# 02_-_CPU.net
KiCad netlist of a schematic drawn in Altium Designer
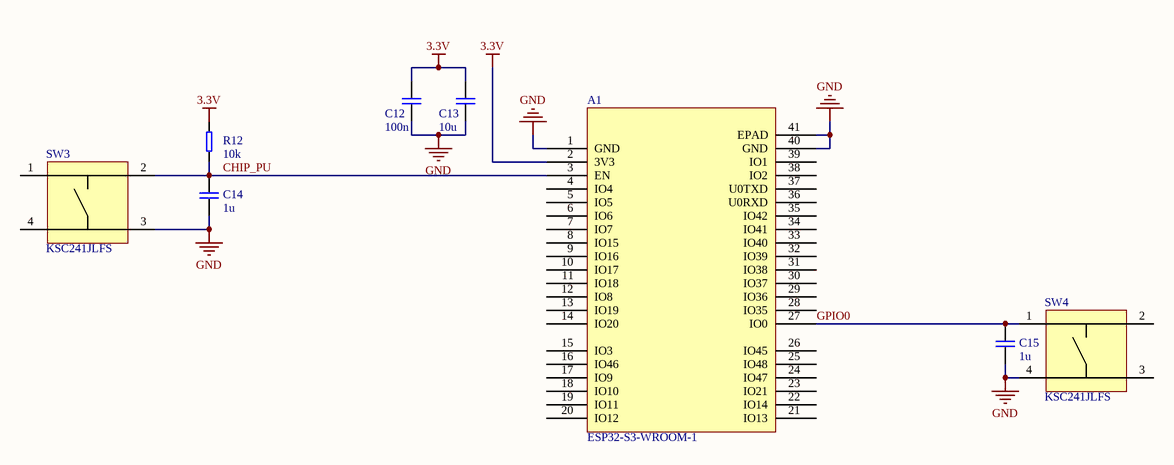
[diagram p0: [02] - CPU.SchDoc]

(export (version "E")
  (design (tool "Eeschema 10.0.6"))
  (components
    (comp (ref "A1")
      (value "ESP32-S3-WROOM-1")
      (footprint "ESP32-S3-WROOM-1")
      (description "2.4 GHz Wi-Fi (802.11 b/g/n) and Bluetooth® 5 (LE) module")
      (fields (field (name "MANUFACTURER") "espressif"))
      (libsource (lib "1") (part "ESP32-S3-WROOM-1"))
    )
    (comp (ref "C12")
      (value "100n")
      (footprint "C0603")
      (description "CAPACITOR")
      (libsource (lib "1") (part "Cap"))
    )
    (comp (ref "C13")
      (value "10u")
      (footprint "C0603")
      (description "CAPACITOR")
      (libsource (lib "1") (part "Cap"))
    )
    (comp (ref "C14")
      (value "1u")
      (footprint "C0603")
      (description "CAPACITOR")
      (libsource (lib "1") (part "Cap"))
    )
    (comp (ref "C15")
      (value "1u")
      (footprint "C0603")
      (description "CAPACITOR")
      (libsource (lib "1") (part "Cap"))
    )
    (comp (ref "R12")
      (value "10k")
      (footprint "R0603")
      (description "RESISTOR")
      (libsource (lib "1") (part "Res"))
    )
    (comp (ref "SW3")
      (value "KSC241JLFS")
      (footprint "KSC241JLFS")
      (description "SWITCH TACTILE SPST-NO 50mA @ 32VDC")
      (fields (field (name "MANUFACTURER") "C&K"))
      (libsource (lib "1") (part "KSC241JLFS"))
    )
    (comp (ref "SW4")
      (value "KSC241JLFS")
      (footprint "KSC241JLFS")
      (description "SWITCH TACTILE SPST-NO 50mA @ 32VDC")
      (fields (field (name "MANUFACTURER") "C&K"))
      (libsource (lib "1") (part "KSC241JLFS"))
    )
  )
  (nets
    (net (code "1") (name "/CHIP_PU") (class "Default")
      (node (ref "A1") (pin "3") (pinfunction "EN_3") (pintype "passive"))
      (node (ref "C14") (pin "1") (pinfunction "1_1") (pintype "passive"))
      (node (ref "R12") (pin "1") (pinfunction "1_1") (pintype "passive"))
      (node (ref "SW3") (pin "2") (pinfunction "2_2") (pintype "passive"))
    )
    (net (code "2") (name "/GPIO0") (class "Default")
      (node (ref "A1") (pin "27") (pinfunction "IO0_27") (pintype "passive"))
      (node (ref "C15") (pin "1") (pinfunction "1_1") (pintype "passive"))
      (node (ref "SW4") (pin "1") (pinfunction "1_1") (pintype "passive"))
    )
    (net (code "3") (name "3.3V") (class "Default")
      (node (ref "A1") (pin "2") (pinfunction "3V3_2") (pintype "passive"))
      (node (ref "C12") (pin "1") (pinfunction "1_1") (pintype "passive"))
      (node (ref "C13") (pin "1") (pinfunction "1_1") (pintype "passive"))
      (node (ref "R12") (pin "2") (pinfunction "2_2") (pintype "passive"))
    )
    (net (code "4") (name "GND") (class "Default")
      (node (ref "A1") (pin "1") (pinfunction "GND_1") (pintype "passive"))
      (node (ref "A1") (pin "40") (pinfunction "GND_40") (pintype "passive"))
      (node (ref "A1") (pin "41") (pinfunction "EPAD_41") (pintype "passive"))
      (node (ref "C12") (pin "2") (pinfunction "2_2") (pintype "passive"))
      (node (ref "C13") (pin "2") (pinfunction "2_2") (pintype "passive"))
      (node (ref "C14") (pin "2") (pinfunction "2_2") (pintype "passive"))
      (node (ref "C15") (pin "2") (pinfunction "2_2") (pintype "passive"))
      (node (ref "SW3") (pin "3") (pinfunction "3_3") (pintype "passive"))
      (node (ref "SW4") (pin "4") (pinfunction "4_4") (pintype "passive"))
    )
    (net (code "5") (name "unconnected-(A1-IO1-Pad39)") (class "Default")
      (node (ref "A1") (pin "39") (pinfunction "IO1_39") (pintype "passive"))
    )
    (net (code "6") (name "unconnected-(A1-IO2-Pad38)") (class "Default")
      (node (ref "A1") (pin "38") (pinfunction "IO2_38") (pintype "passive"))
    )
    (net (code "7") (name "unconnected-(A1-IO3-Pad15)") (class "Default")
      (node (ref "A1") (pin "15") (pinfunction "IO3_15") (pintype "passive"))
    )
    (net (code "8") (name "unconnected-(A1-IO4-Pad4)") (class "Default")
      (node (ref "A1") (pin "4") (pinfunction "IO4_4") (pintype "passive"))
    )
    (net (code "9") (name "unconnected-(A1-IO5-Pad5)") (class "Default")
      (node (ref "A1") (pin "5") (pinfunction "IO5_5") (pintype "passive"))
    )
    (net (code "10") (name "unconnected-(A1-IO6-Pad6)") (class "Default")
      (node (ref "A1") (pin "6") (pinfunction "IO6_6") (pintype "passive"))
    )
    (net (code "11") (name "unconnected-(A1-IO7-Pad7)") (class "Default")
      (node (ref "A1") (pin "7") (pinfunction "IO7_7") (pintype "passive"))
    )
    (net (code "12") (name "unconnected-(A1-IO8-Pad12)") (class "Default")
      (node (ref "A1") (pin "12") (pinfunction "IO8_12") (pintype "passive"))
    )
    (net (code "13") (name "unconnected-(A1-IO9-Pad17)") (class "Default")
      (node (ref "A1") (pin "17") (pinfunction "IO9_17") (pintype "passive"))
    )
    (net (code "14") (name "unconnected-(A1-IO10-Pad18)") (class "Default")
      (node (ref "A1") (pin "18") (pinfunction "IO10_18") (pintype "passive"))
    )
    (net (code "15") (name "unconnected-(A1-IO11-Pad19)") (class "Default")
      (node (ref "A1") (pin "19") (pinfunction "IO11_19") (pintype "passive"))
    )
    (net (code "16") (name "unconnected-(A1-IO12-Pad20)") (class "Default")
      (node (ref "A1") (pin "20") (pinfunction "IO12_20") (pintype "passive"))
    )
    (net (code "17") (name "unconnected-(A1-IO13-Pad21)") (class "Default")
      (node (ref "A1") (pin "21") (pinfunction "IO13_21") (pintype "passive"))
    )
    (net (code "18") (name "unconnected-(A1-IO14-Pad22)") (class "Default")
      (node (ref "A1") (pin "22") (pinfunction "IO14_22") (pintype "passive"))
    )
    (net (code "19") (name "unconnected-(A1-IO15-Pad8)") (class "Default")
      (node (ref "A1") (pin "8") (pinfunction "IO15_8") (pintype "passive"))
    )
    (net (code "20") (name "unconnected-(A1-IO16-Pad9)") (class "Default")
      (node (ref "A1") (pin "9") (pinfunction "IO16_9") (pintype "passive"))
    )
    (net (code "21") (name "unconnected-(A1-IO17-Pad10)") (class "Default")
      (node (ref "A1") (pin "10") (pinfunction "IO17_10") (pintype "passive"))
    )
    (net (code "22") (name "unconnected-(A1-IO18-Pad11)") (class "Default")
      (node (ref "A1") (pin "11") (pinfunction "IO18_11") (pintype "passive"))
    )
    (net (code "23") (name "unconnected-(A1-IO19-Pad13)") (class "Default")
      (node (ref "A1") (pin "13") (pinfunction "IO19_13") (pintype "passive"))
    )
    (net (code "24") (name "unconnected-(A1-IO20-Pad14)") (class "Default")
      (node (ref "A1") (pin "14") (pinfunction "IO20_14") (pintype "passive"))
    )
    (net (code "25") (name "unconnected-(A1-IO21-Pad23)") (class "Default")
      (node (ref "A1") (pin "23") (pinfunction "IO21_23") (pintype "passive"))
    )
    (net (code "26") (name "unconnected-(A1-IO35-Pad28)") (class "Default")
      (node (ref "A1") (pin "28") (pinfunction "IO35_28") (pintype "passive"))
    )
    (net (code "27") (name "unconnected-(A1-IO36-Pad29)") (class "Default")
      (node (ref "A1") (pin "29") (pinfunction "IO36_29") (pintype "passive"))
    )
    (net (code "28") (name "unconnected-(A1-IO37-Pad30)") (class "Default")
      (node (ref "A1") (pin "30") (pinfunction "IO37_30") (pintype "passive"))
    )
    (net (code "29") (name "unconnected-(A1-IO38-Pad31)") (class "Default")
      (node (ref "A1") (pin "31") (pinfunction "IO38_31") (pintype "passive"))
    )
    (net (code "30") (name "unconnected-(A1-IO39-Pad32)") (class "Default")
      (node (ref "A1") (pin "32") (pinfunction "IO39_32") (pintype "passive"))
    )
    (net (code "31") (name "unconnected-(A1-IO40-Pad33)") (class "Default")
      (node (ref "A1") (pin "33") (pinfunction "IO40_33") (pintype "passive"))
    )
    (net (code "32") (name "unconnected-(A1-IO41-Pad34)") (class "Default")
      (node (ref "A1") (pin "34") (pinfunction "IO41_34") (pintype "passive"))
    )
    (net (code "33") (name "unconnected-(A1-IO42-Pad35)") (class "Default")
      (node (ref "A1") (pin "35") (pinfunction "IO42_35") (pintype "passive"))
    )
    (net (code "34") (name "unconnected-(A1-IO45-Pad26)") (class "Default")
      (node (ref "A1") (pin "26") (pinfunction "IO45_26") (pintype "passive"))
    )
    (net (code "35") (name "unconnected-(A1-IO46-Pad16)") (class "Default")
      (node (ref "A1") (pin "16") (pinfunction "IO46_16") (pintype "passive"))
    )
    (net (code "36") (name "unconnected-(A1-IO47-Pad24)") (class "Default")
      (node (ref "A1") (pin "24") (pinfunction "IO47_24") (pintype "passive"))
    )
    (net (code "37") (name "unconnected-(A1-IO48-Pad25)") (class "Default")
      (node (ref "A1") (pin "25") (pinfunction "IO48_25") (pintype "passive"))
    )
    (net (code "38") (name "unconnected-(A1-U0RXD-Pad36)") (class "Default")
      (node (ref "A1") (pin "36") (pinfunction "U0RXD_36") (pintype "passive"))
    )
    (net (code "39") (name "unconnected-(A1-U0TXD-Pad37)") (class "Default")
      (node (ref "A1") (pin "37") (pinfunction "U0TXD_37") (pintype "passive"))
    )
    (net (code "40") (name "unconnected-(SW3-Pad1)") (class "Default")
      (node (ref "SW3") (pin "1") (pinfunction "1_1") (pintype "passive"))
    )
    (net (code "41") (name "unconnected-(SW3-Pad4)") (class "Default")
      (node (ref "SW3") (pin "4") (pinfunction "4_4") (pintype "passive"))
    )
    (net (code "42") (name "unconnected-(SW4-Pad2)") (class "Default")
      (node (ref "SW4") (pin "2") (pinfunction "2_2") (pintype "passive"))
    )
    (net (code "43") (name "unconnected-(SW4-Pad3)") (class "Default")
      (node (ref "SW4") (pin "3") (pinfunction "3_3") (pintype "passive"))
    )
  )
)
